# ATMEGA328P.net
KiCad netlist of a schematic drawn in Altium Designer
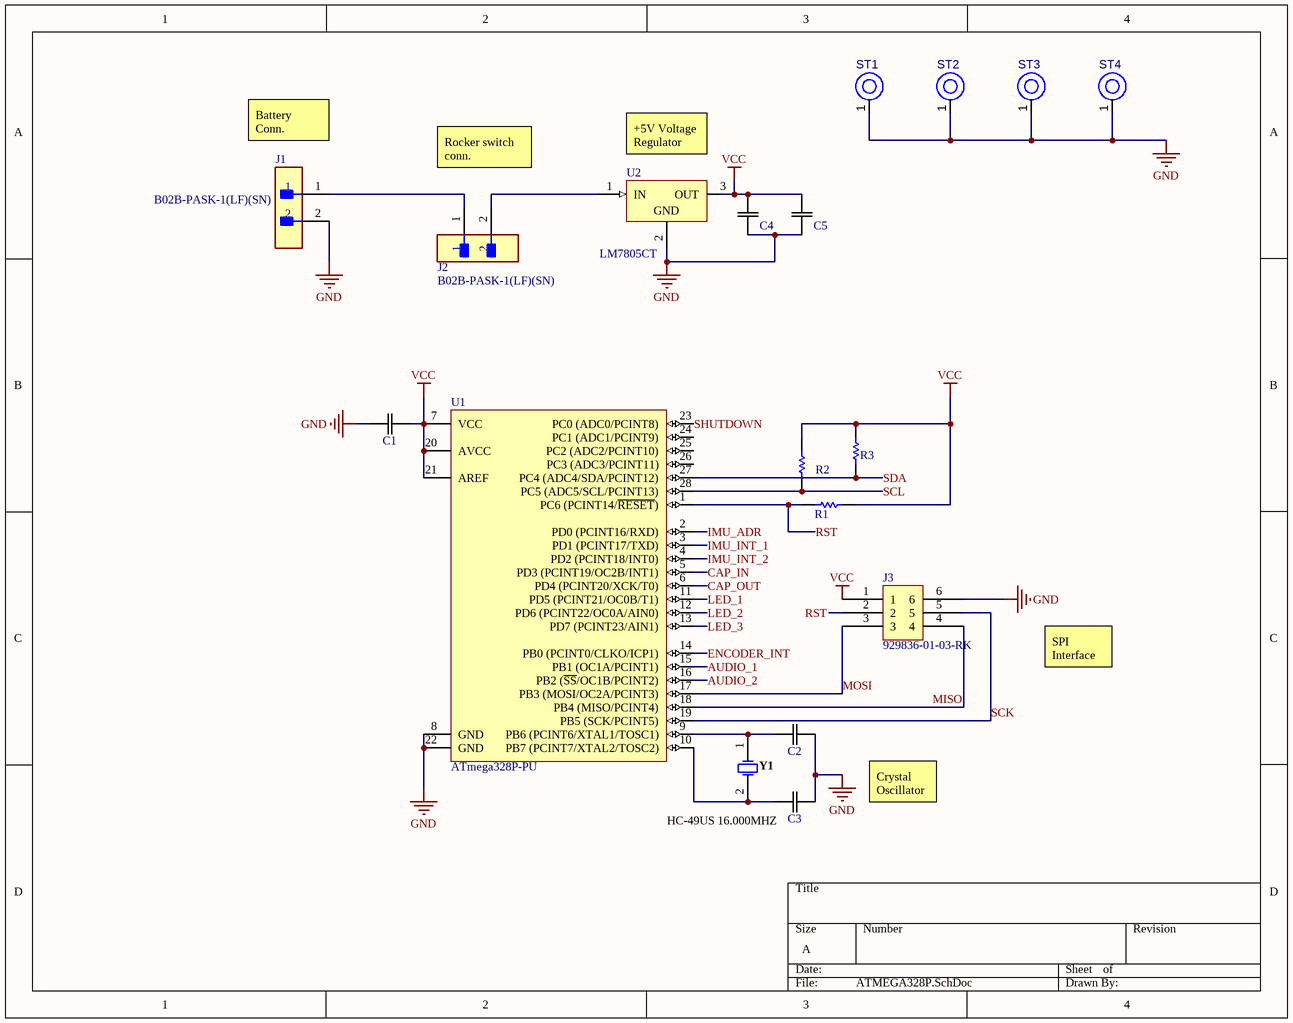
[diagram p0: ATMEGA328P.SchDoc]

(export (version "E")
  (design (tool "Eeschema 10.0.6"))
  (components
    (comp (ref "C1")
      (value "Cap, 22pF, ceramic, TH")
      (footprint "New footprint 1")
      (libsource (lib "University of Pittsburgh") (part "Cap, ceramic"))
    )
    (comp (ref "C2")
      (value "Cap, 22pF, ceramic, TH")
      (footprint "New footprint 1")
      (libsource (lib "University of Pittsburgh") (part "Cap, ceramic"))
    )
    (comp (ref "C3")
      (value "Cap, 22pF, ceramic, TH")
      (footprint "New footprint 1")
      (libsource (lib "University of Pittsburgh") (part "Cap, ceramic"))
    )
    (comp (ref "C4")
      (value "Cap, 22pF, ceramic, TH")
      (footprint "New footprint 1")
      (libsource (lib "University of Pittsburgh") (part "Cap, ceramic"))
    )
    (comp (ref "C5")
      (value "Cap, 22pF, ceramic, TH")
      (footprint "New footprint 1")
      (libsource (lib "University of Pittsburgh") (part "Cap, ceramic"))
    )
    (comp (ref "J1")
      (value "B02B-PASK-1(LF)(SN)")
      (footprint "FP-B02B-PASK-1_LF_SN-MFG")
      (description "CONN HEADER VERT 2POS 2MM")
      (libsource (lib "") (part "3bc925449376181038e59eaffc5286c_1"))
    )
    (comp (ref "J2")
      (value "B02B-PASK-1(LF)(SN)")
      (footprint "FP-B02B-PASK-1_LF_SN-MFG")
      (description "CONN HEADER VERT 2POS 2MM")
      (libsource (lib "Altium Content Vault") (part "3bc925449376181038e59eaffc5286c"))
    )
    (comp (ref "J3")
      (value "929836-01-03-RK")
      (footprint "929836-01-03-RK-Footprint-1")
      (description "3x2 male header")
      (libsource (lib "University of Pittsburgh") (part "929836-01-03-RK-Symbol-1"))
    )
    (comp (ref "R1")
      (value "1k Through-Hole 1/4W")
      (footprint "RESA60-630X240")
      (description "RES 1K OHM 1/4W 1% AXIAL")
      (fields (field (name "TOLERANCE") "1%"))
      (libsource (lib "University of Pittsburgh") (part "RES-2"))
    )
    (comp (ref "R2")
      (value "1k Through-Hole 1/4W")
      (footprint "RESA60-630X240")
      (description "RES 1K OHM 1/4W 1% AXIAL")
      (fields (field (name "TOLERANCE") "1%"))
      (libsource (lib "University of Pittsburgh") (part "RES-2"))
    )
    (comp (ref "R3")
      (value "1k Through-Hole 1/4W")
      (footprint "RESA60-630X240")
      (description "RES 1K OHM 1/4W 1% AXIAL")
      (fields (field (name "TOLERANCE") "1%"))
      (libsource (lib "University of Pittsburgh") (part "RES-2"))
    )
    (comp (ref "ST1")
      (value "PTH-M2D5X5")
      (footprint "PTH-M2D5X5")
      (description "M2 PTH (2.5mm), 5mm pad")
      (libsource (lib "University of Pittsburgh") (part "CMP-00028-00000-1"))
    )
    (comp (ref "ST2")
      (value "PTH-M2D5X5")
      (footprint "PTH-M2D5X5")
      (description "M2 PTH (2.5mm), 5mm pad")
      (libsource (lib "University of Pittsburgh") (part "CMP-00028-00000-1"))
    )
    (comp (ref "ST3")
      (value "PTH-M2D5X5")
      (footprint "PTH-M2D5X5")
      (description "M2 PTH (2.5mm), 5mm pad")
      (libsource (lib "University of Pittsburgh") (part "CMP-00028-00000-1"))
    )
    (comp (ref "ST4")
      (value "PTH-M2D5X5")
      (footprint "PTH-M2D5X5")
      (description "M2 PTH (2.5mm), 5mm pad")
      (libsource (lib "University of Pittsburgh") (part "CMP-00028-00000-1"))
    )
    (comp (ref "U1")
      (value "ATmega328P-PU")
      (footprint "28P3")
      (libsource (lib "Altium Content Vault") (part "MC-8B-ATM48-IL28"))
    )
    (comp (ref "U2")
      (value "LM7805CT")
      (footprint "FAIR-TO-220-3")
      (description "Positive Voltage Regulator, 5 V, 1 A, -40 to 125 degC, 3-Pin TO-220, RoHS, Tube")
      (fields (field (name "MANUFACTURER") "FairchildSemiconductor"))
      (libsource (lib "Altium Content Vault") (part "FAIR-LM7805CT-TO220-3"))
    )
    (comp (ref "Y1")
      (value "HC-49US 16.000MHZ")
      (footprint "JPY-HC-49US")
      (description "Crystal, 16 MHz, +/- 30 ppm, 18 pF, -20 to 70 degC, 2-Pin THD")
      (fields (field (name "MANUFACTURER") "Jing peng yuan"))
      (libsource (lib "University of Pittsburgh") (part "XTAL-1-2-2"))
    )
  )
  (nets
    (net (code "1") (name "/AUDIO_1") (class "Default")
      (node (ref "U1") (pin "15") (pinfunction "PB1_(OC1A/PCINT1)_15") (pintype "bidirectional"))
    )
    (net (code "2") (name "/AUDIO_2") (class "Default")
      (node (ref "U1") (pin "16") (pinfunction "PB2_(~{SS}/OC1B/PCINT2)_16") (pintype "bidirectional"))
    )
    (net (code "3") (name "/CAP_IN") (class "Default")
      (node (ref "U1") (pin "5") (pinfunction "PD3_(PCINT19/OC2B/INT1)_5") (pintype "bidirectional"))
    )
    (net (code "4") (name "/CAP_OUT") (class "Default")
      (node (ref "U1") (pin "6") (pinfunction "PD4_(PCINT20/XCK/T0)_6") (pintype "bidirectional"))
    )
    (net (code "5") (name "/ENCODER_INT") (class "Default")
      (node (ref "U1") (pin "14") (pinfunction "PB0_(PCINT0/CLKO/ICP1)_14") (pintype "bidirectional"))
    )
    (net (code "6") (name "/IMU_ADR") (class "Default")
      (node (ref "U1") (pin "2") (pinfunction "PD0_(PCINT16/RXD)_2") (pintype "bidirectional"))
    )
    (net (code "7") (name "/IMU_INT_1") (class "Default")
      (node (ref "U1") (pin "3") (pinfunction "PD1_(PCINT17/TXD)_3") (pintype "bidirectional"))
    )
    (net (code "8") (name "/IMU_INT_2") (class "Default")
      (node (ref "U1") (pin "4") (pinfunction "PD2_(PCINT18/INT0)_4") (pintype "bidirectional"))
    )
    (net (code "9") (name "/LED_1") (class "Default")
      (node (ref "U1") (pin "11") (pinfunction "PD5_(PCINT21/OC0B/T1)_11") (pintype "bidirectional"))
    )
    (net (code "10") (name "/LED_2") (class "Default")
      (node (ref "U1") (pin "12") (pinfunction "PD6_(PCINT22/OC0A/AIN0)_12") (pintype "bidirectional"))
    )
    (net (code "11") (name "/LED_3") (class "Default")
      (node (ref "U1") (pin "13") (pinfunction "PD7_(PCINT23/AIN1)_13") (pintype "bidirectional"))
    )
    (net (code "12") (name "/MISO") (class "Default")
      (node (ref "J3") (pin "4") (pinfunction "4_4") (pintype "passive"))
      (node (ref "U1") (pin "18") (pinfunction "PB4_(MISO/PCINT4)_18") (pintype "bidirectional"))
    )
    (net (code "13") (name "/MOSI") (class "Default")
      (node (ref "J3") (pin "3") (pinfunction "3_3") (pintype "passive"))
      (node (ref "U1") (pin "17") (pinfunction "PB3_(MOSI/OC2A/PCINT3)_17") (pintype "bidirectional"))
    )
    (net (code "14") (name "/RST") (class "Default")
      (node (ref "J3") (pin "2") (pinfunction "2_2") (pintype "passive"))
      (node (ref "R1") (pin "1") (pinfunction "1_1") (pintype "passive"))
      (node (ref "U1") (pin "1") (pinfunction "PC6_(PCINT14/~{RESET})_1") (pintype "bidirectional"))
    )
    (net (code "15") (name "/SCK") (class "Default")
      (node (ref "J3") (pin "5") (pinfunction "5_5") (pintype "passive"))
      (node (ref "U1") (pin "19") (pinfunction "PB5_(SCK/PCINT5)_19") (pintype "bidirectional"))
    )
    (net (code "16") (name "/SCL") (class "Default")
      (node (ref "R2") (pin "1") (pinfunction "1_1") (pintype "passive"))
      (node (ref "U1") (pin "28") (pinfunction "PC5_(ADC5/SCL/PCINT13)_28") (pintype "bidirectional"))
    )
    (net (code "17") (name "/SDA") (class "Default")
      (node (ref "R3") (pin "1") (pinfunction "1_1") (pintype "passive"))
      (node (ref "U1") (pin "27") (pinfunction "PC4_(ADC4/SDA/PCINT12)_27") (pintype "bidirectional"))
    )
    (net (code "18") (name "/SHUTDOWN") (class "Default")
      (node (ref "U1") (pin "23") (pinfunction "PC0_(ADC0/PCINT8)_23") (pintype "bidirectional"))
    )
    (net (code "19") (name "GND") (class "Default")
      (node (ref "C1") (pin "1") (pinfunction "1_1") (pintype "passive"))
      (node (ref "C2") (pin "2") (pinfunction "2_2") (pintype "passive"))
      (node (ref "C3") (pin "2") (pinfunction "2_2") (pintype "passive"))
      (node (ref "C4") (pin "2") (pinfunction "2_2") (pintype "passive"))
      (node (ref "C5") (pin "2") (pinfunction "2_2") (pintype "passive"))
      (node (ref "J1") (pin "2") (pinfunction "2_2") (pintype "passive"))
      (node (ref "J3") (pin "6") (pinfunction "6_6") (pintype "passive"))
      (node (ref "ST1") (pin "1") (pinfunction "H1_1") (pintype "passive"))
      (node (ref "ST2") (pin "1") (pinfunction "H1_1") (pintype "passive"))
      (node (ref "ST3") (pin "1") (pinfunction "H1_1") (pintype "passive"))
      (node (ref "ST4") (pin "1") (pinfunction "H1_1") (pintype "passive"))
      (node (ref "U1") (pin "22") (pinfunction "GND_22") (pintype "power_in"))
      (node (ref "U1") (pin "8") (pinfunction "GND_8") (pintype "power_in"))
      (node (ref "U2") (pin "2") (pinfunction "GND_2") (pintype "power_in"))
    )
    (net (code "20") (name "Net-(J1-Pad1)") (class "Default")
      (node (ref "J1") (pin "1") (pinfunction "1_1") (pintype "passive"))
      (node (ref "J2") (pin "1") (pinfunction "1_1") (pintype "passive"))
    )
    (net (code "21") (name "Net-(U1-PB6_(PCINT6{slash}XTAL1{slash}TOSC1))") (class "Default")
      (node (ref "C2") (pin "1") (pinfunction "1_1") (pintype "passive"))
      (node (ref "U1") (pin "9") (pinfunction "PB6_(PCINT6/XTAL1/TOSC1)_9") (pintype "bidirectional"))
      (node (ref "Y1") (pin "1") (pinfunction "1_1") (pintype "passive"))
    )
    (net (code "22") (name "Net-(U1-PB7_(PCINT7{slash}XTAL2{slash}TOSC2))") (class "Default")
      (node (ref "C3") (pin "1") (pinfunction "1_1") (pintype "passive"))
      (node (ref "U1") (pin "10") (pinfunction "PB7_(PCINT7/XTAL2/TOSC2)_10") (pintype "bidirectional"))
      (node (ref "Y1") (pin "2") (pinfunction "2_2") (pintype "passive"))
    )
    (net (code "23") (name "Net-(U2-IN)") (class "Default")
      (node (ref "J2") (pin "2") (pinfunction "2_2") (pintype "passive"))
      (node (ref "U2") (pin "1") (pinfunction "IN_1") (pintype "input"))
    )
    (net (code "24") (name "VCC") (class "Default")
      (node (ref "C1") (pin "2") (pinfunction "2_2") (pintype "passive"))
      (node (ref "C4") (pin "1") (pinfunction "1_1") (pintype "passive"))
      (node (ref "C5") (pin "1") (pinfunction "1_1") (pintype "passive"))
      (node (ref "J3") (pin "1") (pinfunction "1_1") (pintype "passive"))
      (node (ref "R1") (pin "2") (pinfunction "2_2") (pintype "passive"))
      (node (ref "R2") (pin "2") (pinfunction "2_2") (pintype "passive"))
      (node (ref "R3") (pin "2") (pinfunction "2_2") (pintype "passive"))
      (node (ref "U1") (pin "20") (pinfunction "AVCC_20") (pintype "power_in"))
      (node (ref "U1") (pin "21") (pinfunction "AREF_21") (pintype "power_in"))
      (node (ref "U1") (pin "7") (pinfunction "VCC_7") (pintype "power_in"))
      (node (ref "U2") (pin "3") (pinfunction "OUT_3") (pintype "passive"))
    )
    (net (code "25") (name "unconnected-(U1-PC1_(ADC1{slash}PCINT9)-Pad24)") (class "Default")
      (node (ref "U1") (pin "24") (pinfunction "PC1_(ADC1/PCINT9)_24") (pintype "bidirectional"))
    )
    (net (code "26") (name "unconnected-(U1-PC2_(ADC2{slash}PCINT10)-Pad25)") (class "Default")
      (node (ref "U1") (pin "25") (pinfunction "PC2_(ADC2/PCINT10)_25") (pintype "bidirectional"))
    )
    (net (code "27") (name "unconnected-(U1-PC3_(ADC3{slash}PCINT11)-Pad26)") (class "Default")
      (node (ref "U1") (pin "26") (pinfunction "PC3_(ADC3/PCINT11)_26") (pintype "bidirectional"))
    )
  )
)
